# faun-two-layer-lipo-v1_0.net
KiCad netlist of a schematic drawn in EAGLE
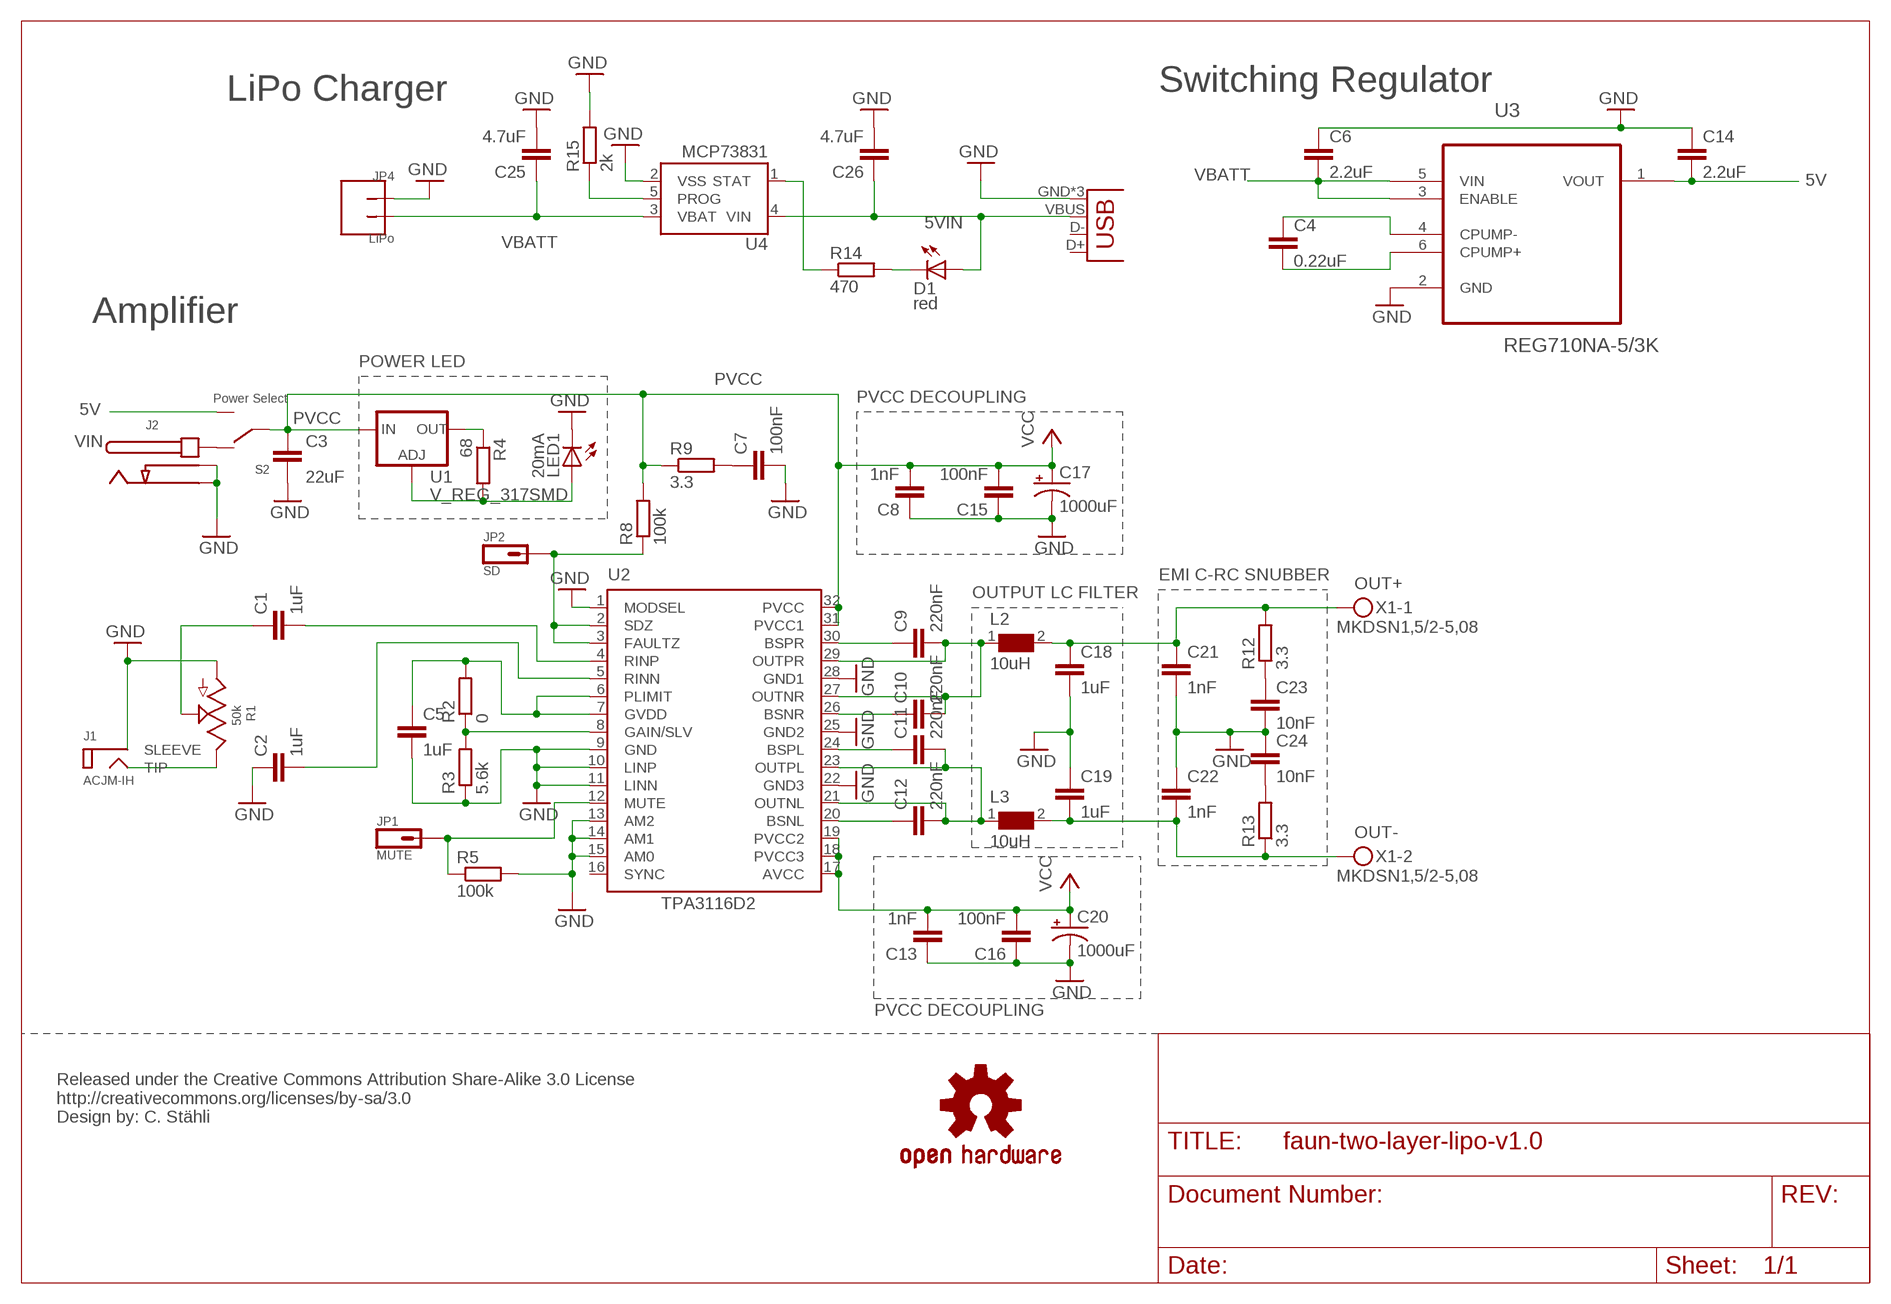
[diagram p0: schematic, sheet 1]

(export (version "E")
  (design (tool "Eeschema 10.0.6"))
  (components
    (comp (ref "C1")
      (value "1uF")
      (footprint "eagle-import:C1206")
      (libsource (lib "eagle-import") (part "C-EUC1206"))
    )
    (comp (ref "C2")
      (value "1uF")
      (footprint "eagle-import:C1206")
      (libsource (lib "eagle-import") (part "C-EUC1206"))
    )
    (comp (ref "C3")
      (value "22uF")
      (footprint "eagle-import:C1206")
      (libsource (lib "eagle-import") (part "C-EUC1206"))
    )
    (comp (ref "C4")
      (value "0.22uF")
      (footprint "eagle-import:C1206")
      (libsource (lib "eagle-import") (part "C-EUC1206"))
    )
    (comp (ref "C5")
      (value "1uF")
      (footprint "eagle-import:C1206")
      (libsource (lib "eagle-import") (part "C-EUC1206"))
    )
    (comp (ref "C6")
      (value "2.2uF")
      (footprint "eagle-import:C1206")
      (libsource (lib "eagle-import") (part "C-EUC1206"))
    )
    (comp (ref "C7")
      (value "100nF")
      (footprint "eagle-import:C1206")
      (libsource (lib "eagle-import") (part "C-EUC1206"))
    )
    (comp (ref "C8")
      (value "1nF")
      (footprint "eagle-import:C1206")
      (libsource (lib "eagle-import") (part "C-EUC1206"))
    )
    (comp (ref "C9")
      (value "220nF")
      (footprint "eagle-import:C1206")
      (libsource (lib "eagle-import") (part "C-EUC1206"))
    )
    (comp (ref "C10")
      (value "220nF")
      (footprint "eagle-import:C1206")
      (libsource (lib "eagle-import") (part "C-EUC1206"))
    )
    (comp (ref "C11")
      (value "220nF")
      (footprint "eagle-import:C1206")
      (libsource (lib "eagle-import") (part "C-EUC1206"))
    )
    (comp (ref "C12")
      (value "220nF")
      (footprint "eagle-import:C1206")
      (libsource (lib "eagle-import") (part "C-EUC1206"))
    )
    (comp (ref "C13")
      (value "1nF")
      (footprint "eagle-import:C1206")
      (libsource (lib "eagle-import") (part "C-EUC1206"))
    )
    (comp (ref "C14")
      (value "2.2uF")
      (footprint "eagle-import:C1206")
      (libsource (lib "eagle-import") (part "C-EUC1206"))
    )
    (comp (ref "C15")
      (value "100nF")
      (footprint "eagle-import:C1206")
      (libsource (lib "eagle-import") (part "C-EUC1206"))
    )
    (comp (ref "C16")
      (value "100nF")
      (footprint "eagle-import:C1206")
      (libsource (lib "eagle-import") (part "C-EUC1206"))
    )
    (comp (ref "C17")
      (value "1000uF")
      (footprint "eagle-import:UES1E102MHM")
      (libsource (lib "eagle-import") (part "UES1E102MHM"))
    )
    (comp (ref "C18")
      (value "1uF")
      (footprint "eagle-import:C1206")
      (libsource (lib "eagle-import") (part "C-EUC1206"))
    )
    (comp (ref "C19")
      (value "1uF")
      (footprint "eagle-import:C1206")
      (libsource (lib "eagle-import") (part "C-EUC1206"))
    )
    (comp (ref "C20")
      (value "1000uF")
      (footprint "eagle-import:UES1E102MHM")
      (libsource (lib "eagle-import") (part "UES1E102MHM"))
    )
    (comp (ref "C21")
      (value "1nF")
      (footprint "eagle-import:C1206")
      (libsource (lib "eagle-import") (part "C-EUC1206"))
    )
    (comp (ref "C22")
      (value "1nF")
      (footprint "eagle-import:C1206")
      (libsource (lib "eagle-import") (part "C-EUC1206"))
    )
    (comp (ref "C23")
      (value "10nF")
      (footprint "eagle-import:C1206")
      (libsource (lib "eagle-import") (part "C-EUC1206"))
    )
    (comp (ref "C24")
      (value "10nF")
      (footprint "eagle-import:C1206")
      (libsource (lib "eagle-import") (part "C-EUC1206"))
    )
    (comp (ref "C25")
      (value "4.7uF")
      (footprint "eagle-import:C1206")
      (libsource (lib "eagle-import") (part "C-EUC1206"))
    )
    (comp (ref "C26")
      (value "4.7uF")
      (footprint "eagle-import:C1206")
      (libsource (lib "eagle-import") (part "C-EUC1206"))
    )
    (comp (ref "D1")
      (value "red")
      (footprint "eagle-import:LED-1206")
      (libsource (lib "eagle-import") (part "LED1206"))
    )
    (comp (ref "J1")
      (value "ACJM-IH")
      (footprint "eagle-import:ACJM-IH")
      (libsource (lib "eagle-import") (part "ACJM-IH"))
    )
    (comp (ref "J2")
      (value "PJ-102AH")
      (footprint "eagle-import:PJ-102AH")
      (libsource (lib "eagle-import") (part "PJ-102AH"))
    )
    (comp (ref "JP1")
      (value "MUTE")
      (footprint "eagle-import:PAD-1.5X4.5")
      (libsource (lib "eagle-import") (part "M01SMD-4.5X1.5"))
    )
    (comp (ref "JP2")
      (value "SD")
      (footprint "eagle-import:PAD-1.5X4.5")
      (libsource (lib "eagle-import") (part "M01SMD-4.5X1.5"))
    )
    (comp (ref "JP4")
      (value "LiPo")
      (footprint "eagle-import:1778764")
      (libsource (lib "eagle-import") (part "1778764"))
    )
    (comp (ref "L2")
      (value "10uH")
      (footprint "eagle-import:WE-PD_1260_1245_1280_1210")
      (libsource (lib "eagle-import") (part "WE-PD_1260/1245/1280/1210"))
    )
    (comp (ref "L3")
      (value "10uH")
      (footprint "eagle-import:WE-PD_1260_1245_1280_1210")
      (libsource (lib "eagle-import") (part "WE-PD_1260/1245/1280/1210"))
    )
    (comp (ref "LED1")
      (value "20mA")
      (footprint "eagle-import:LED-1206")
      (libsource (lib "eagle-import") (part "faun_LED1206"))
    )
    (comp (ref "OPEN_HARDWARE_LOGO")
      (value "OSHW-LOGOL")
      (footprint "eagle-import:OSHW-LOGO-L")
      (libsource (lib "eagle-import") (part "OSHW-LOGOL"))
    )
    (comp (ref "OPEN_HARDWARE_LOGO_TOP")
      (value "OSHW-LOGOL")
      (footprint "eagle-import:OSHW-LOGO-L")
      (libsource (lib "eagle-import") (part "OSHW-LOGOL"))
    )
    (comp (ref "R1")
      (value "50k")
      (footprint "eagle-import:PTD902-2015K")
      (libsource (lib "eagle-import") (part "PTD902-2015K-A503"))
    )
    (comp (ref "R2")
      (value "0")
      (footprint "eagle-import:R1206")
      (libsource (lib "eagle-import") (part "R-EU_R1206"))
    )
    (comp (ref "R3")
      (value "5.6k")
      (footprint "eagle-import:R1206")
      (libsource (lib "eagle-import") (part "R-EU_R1206"))
    )
    (comp (ref "R4")
      (value "68")
      (footprint "eagle-import:R1206")
      (libsource (lib "eagle-import") (part "R-EU_R1206"))
    )
    (comp (ref "R5")
      (value "100k")
      (footprint "eagle-import:R1206")
      (libsource (lib "eagle-import") (part "R-EU_R1206"))
    )
    (comp (ref "R8")
      (value "100k")
      (footprint "eagle-import:R1206")
      (libsource (lib "eagle-import") (part "R-EU_R1206"))
    )
    (comp (ref "R9")
      (value "3.3")
      (footprint "eagle-import:R1206")
      (libsource (lib "eagle-import") (part "R-EU_R1206"))
    )
    (comp (ref "R12")
      (value "3.3")
      (footprint "eagle-import:R1206")
      (libsource (lib "eagle-import") (part "R-EU_R1206"))
    )
    (comp (ref "R13")
      (value "3.3")
      (footprint "eagle-import:R1206")
      (libsource (lib "eagle-import") (part "R-EU_R1206"))
    )
    (comp (ref "R14")
      (value "470")
      (footprint "eagle-import:R1206")
      (libsource (lib "eagle-import") (part "R-EU_R1206"))
    )
    (comp (ref "R15")
      (value "2k")
      (footprint "eagle-import:R1206")
      (libsource (lib "eagle-import") (part "R-EU_R1206"))
    )
    (comp (ref "S2")
      (value "Power Select")
      (footprint "eagle-import:MS-100845")
      (libsource (lib "eagle-import") (part "MS-100845"))
    )
    (comp (ref "U1")
      (value "V_REG_317SMD")
      (footprint "eagle-import:SOT223")
      (libsource (lib "eagle-import") (part "V_REG_317SMD"))
    )
    (comp (ref "U2")
      (value "TPA3116D2")
      (footprint "eagle-import:TPA3116D2")
      (libsource (lib "eagle-import") (part "TPA3116D2"))
    )
    (comp (ref "U3")
      (value "REG710NA-5/3K")
      (footprint "eagle-import:SOT95P280X145-6N")
      (libsource (lib "eagle-import") (part "REG710NA-5/3K"))
    )
    (comp (ref "U4")
      (value "MCP73831")
      (footprint "eagle-import:SOT23-5")
      (libsource (lib "eagle-import") (part "MCP73831"))
    )
    (comp (ref "X1")
      (value "MKDSN1,5/2-5,08")
      (footprint "eagle-import:MKDSN1,5_2-5,08")
      (fields (field (name "MPN") "MKDSN 1,5/2-5.08"))
      (libsource (lib "eagle-import") (part "MKDSN1,5/2-5,08"))
    )
    (comp (ref "X2")
      (value "USB-MICROB")
      (footprint "eagle-import:USB-MICROB")
      (libsource (lib "eagle-import") (part "USB-MICROB"))
    )
  )
  (nets
    (net (code "1") (name "/5V") (class "Default")
      (node (ref "C14") (pin "2") (pinfunction "2_2") (pintype "passive"))
      (node (ref "S2") (pin "P$3") (pinfunction "P$3_P$3") (pintype "input"))
      (node (ref "U3") (pin "1") (pinfunction "VOUT_1") (pintype "output"))
    )
    (net (code "2") (name "/5VIN") (class "Default")
      (node (ref "C26") (pin "1") (pinfunction "1_1") (pintype "passive"))
      (node (ref "D1") (pin "A") (pinfunction "A_A") (pintype "passive"))
      (node (ref "U4") (pin "4") (pinfunction "VIN_4") (pintype "power_in"))
      (node (ref "X2") (pin "VBUS") (pinfunction "VBUS_VBUS") (pintype "bidirectional"))
    )
    (net (code "3") (name "/OUT+") (class "Default")
      (node (ref "C18") (pin "1") (pinfunction "1_1") (pintype "passive"))
      (node (ref "C21") (pin "1") (pinfunction "1_1") (pintype "passive"))
      (node (ref "L2") (pin "2") (pinfunction "2_2") (pintype "passive"))
      (node (ref "R12") (pin "2") (pinfunction "2_2") (pintype "passive"))
      (node (ref "X1") (pin "1") (pinfunction "KL_1") (pintype "passive"))
    )
    (net (code "4") (name "/OUT-") (class "Default")
      (node (ref "C19") (pin "2") (pinfunction "2_2") (pintype "passive"))
      (node (ref "C22") (pin "2") (pinfunction "2_2") (pintype "passive"))
      (node (ref "L3") (pin "2") (pinfunction "2_2") (pintype "passive"))
      (node (ref "R13") (pin "1") (pinfunction "1_1") (pintype "passive"))
      (node (ref "X1") (pin "2") (pinfunction "KL_2") (pintype "passive"))
    )
    (net (code "5") (name "/VBATT") (class "Default")
      (node (ref "C25") (pin "1") (pinfunction "1_1") (pintype "passive"))
      (node (ref "C6") (pin "2") (pinfunction "2_2") (pintype "passive"))
      (node (ref "JP4") (pin "2") (pinfunction "2_2") (pintype "bidirectional"))
      (node (ref "U3") (pin "3") (pinfunction "ENABLE_3") (pintype "input"))
      (node (ref "U3") (pin "5") (pinfunction "VIN_5") (pintype "input"))
      (node (ref "U4") (pin "3") (pinfunction "VBAT_3") (pintype "power_in"))
    )
    (net (code "7") (name "/VIN") (class "Default")
      (node (ref "J2") (pin "VCC") (pinfunction "P$1_VCC") (pintype "bidirectional"))
      (node (ref "S2") (pin "P$1") (pinfunction "P$1_P$1") (pintype "input"))
    )
    (net (code "8") (name "GND") (class "Default")
      (node (ref "C13") (pin "1") (pinfunction "1_1") (pintype "passive"))
      (node (ref "C14") (pin "1") (pinfunction "1_1") (pintype "passive"))
      (node (ref "C15") (pin "1") (pinfunction "1_1") (pintype "passive"))
      (node (ref "C16") (pin "1") (pinfunction "1_1") (pintype "passive"))
      (node (ref "C17") (pin "-") (pinfunction "-_-") (pintype "passive"))
      (node (ref "C18") (pin "2") (pinfunction "2_2") (pintype "passive"))
      (node (ref "C19") (pin "1") (pinfunction "1_1") (pintype "passive"))
      (node (ref "C2") (pin "1") (pinfunction "1_1") (pintype "passive"))
      (node (ref "C20") (pin "-") (pinfunction "-_-") (pintype "passive"))
      (node (ref "C21") (pin "2") (pinfunction "2_2") (pintype "passive"))
      (node (ref "C22") (pin "1") (pinfunction "1_1") (pintype "passive"))
      (node (ref "C23") (pin "2") (pinfunction "2_2") (pintype "passive"))
      (node (ref "C24") (pin "1") (pinfunction "1_1") (pintype "passive"))
      (node (ref "C25") (pin "2") (pinfunction "2_2") (pintype "passive"))
      (node (ref "C26") (pin "2") (pinfunction "2_2") (pintype "passive"))
      (node (ref "C3") (pin "2") (pinfunction "2_2") (pintype "passive"))
      (node (ref "C5") (pin "2") (pinfunction "2_2") (pintype "passive"))
      (node (ref "C6") (pin "1") (pinfunction "1_1") (pintype "passive"))
      (node (ref "C7") (pin "2") (pinfunction "2_2") (pintype "passive"))
      (node (ref "C8") (pin "1") (pinfunction "1_1") (pintype "passive"))
      (node (ref "J1") (pin "SLEEVE@1") (pinfunction "SLEEVE_SLEEVE@1") (pintype "bidirectional"))
      (node (ref "J1") (pin "SLEEVE@2") (pinfunction "SLEEVE_SLEEVE@2") (pintype "bidirectional"))
      (node (ref "J2") (pin "GND@1") (pinfunction "P$2_GND@1") (pintype "bidirectional"))
      (node (ref "J2") (pin "GND@2") (pinfunction "P$3_GND@2") (pintype "bidirectional"))
      (node (ref "JP4") (pin "1") (pinfunction "1_1") (pintype "output"))
      (node (ref "LED1") (pin "C") (pinfunction "C_C") (pintype "passive"))
      (node (ref "R1") (pin "1") (pinfunction "1_1") (pintype "bidirectional"))
      (node (ref "R1") (pin "1'") (pinfunction "1_1'") (pintype "bidirectional"))
      (node (ref "R15") (pin "2") (pinfunction "2_2") (pintype "passive"))
      (node (ref "R3") (pin "1") (pinfunction "1_1") (pintype "passive"))
      (node (ref "R5") (pin "2") (pinfunction "2_2") (pintype "passive"))
      (node (ref "U2") (pin "1") (pinfunction "MODSEL_1") (pintype "input"))
      (node (ref "U2") (pin "10") (pinfunction "LINP_10") (pintype "input"))
      (node (ref "U2") (pin "11") (pinfunction "LINN_11") (pintype "input"))
      (node (ref "U2") (pin "13") (pinfunction "AM2_13") (pintype "input"))
      (node (ref "U2") (pin "14") (pinfunction "AM1_14") (pintype "input"))
      (node (ref "U2") (pin "15") (pinfunction "AM0_15") (pintype "input"))
      (node (ref "U2") (pin "22") (pinfunction "GND3_22") (pintype "input"))
      (node (ref "U2") (pin "25") (pinfunction "GND2_25") (pintype "input"))
      (node (ref "U2") (pin "28") (pinfunction "GND1_28") (pintype "input"))
      (node (ref "U2") (pin "9") (pinfunction "GND_9") (pintype "input"))
      (node (ref "U3") (pin "2") (pinfunction "GND_2") (pintype "passive"))
      (node (ref "U4") (pin "2") (pinfunction "VSS_2") (pintype "power_in"))
      (node (ref "X2") (pin "GND") (pinfunction "GND_GND") (pintype "bidirectional"))
      (node (ref "X2") (pin "MT1") (pinfunction "GND_MT1") (pintype "bidirectional"))
      (node (ref "X2") (pin "MT2") (pinfunction "GND_MT2") (pintype "bidirectional"))
    )
    (net (code "9") (name "Net-(C1-Pad1)") (class "Default")
      (node (ref "C1") (pin "1") (pinfunction "1_1") (pintype "passive"))
      (node (ref "R1") (pin "2") (pinfunction "2_2") (pintype "bidirectional"))
      (node (ref "R1") (pin "2'") (pinfunction "2_2'") (pintype "bidirectional"))
    )
    (net (code "10") (name "Net-(C7-Pad1)") (class "Default")
      (node (ref "C7") (pin "1") (pinfunction "1_1") (pintype "passive"))
      (node (ref "R9") (pin "2") (pinfunction "2_2") (pintype "passive"))
    )
    (net (code "11") (name "Net-(C23-Pad1)") (class "Default")
      (node (ref "C23") (pin "1") (pinfunction "1_1") (pintype "passive"))
      (node (ref "R12") (pin "1") (pinfunction "1_1") (pintype "passive"))
    )
    (net (code "12") (name "Net-(C24-Pad2)") (class "Default")
      (node (ref "C24") (pin "2") (pinfunction "2_2") (pintype "passive"))
      (node (ref "R13") (pin "2") (pinfunction "2_2") (pintype "passive"))
    )
    (net (code "13") (name "Net-(D1-PadC)") (class "Default")
      (node (ref "D1") (pin "C") (pinfunction "C_C") (pintype "passive"))
      (node (ref "R14") (pin "2") (pinfunction "2_2") (pintype "passive"))
    )
    (net (code "14") (name "Net-(J1-TIP-PadTIP@1)") (class "Default")
      (node (ref "J1") (pin "TIP@1") (pinfunction "TIP_TIP@1") (pintype "input"))
      (node (ref "J1") (pin "TIP@2") (pinfunction "TIP_TIP@2") (pintype "input"))
      (node (ref "R1") (pin "3") (pinfunction "3_3") (pintype "bidirectional"))
      (node (ref "R1") (pin "3'") (pinfunction "3_3'") (pintype "bidirectional"))
    )
    (net (code "15") (name "Net-(JP1-1)") (class "Default")
      (node (ref "JP1") (pin "P$1") (pinfunction "1_P$1") (pintype "passive"))
      (node (ref "R5") (pin "1") (pinfunction "1_1") (pintype "passive"))
      (node (ref "U2") (pin "12") (pinfunction "MUTE_12") (pintype "input"))
    )
    (net (code "16") (name "Net-(JP2-1)") (class "Default")
      (node (ref "JP2") (pin "P$1") (pinfunction "1_P$1") (pintype "passive"))
      (node (ref "R8") (pin "1") (pinfunction "1_1") (pintype "passive"))
      (node (ref "U2") (pin "2") (pinfunction "SDZ_2") (pintype "input"))
      (node (ref "U2") (pin "3") (pinfunction "FAULTZ_3") (pintype "input"))
    )
    (net (code "17") (name "Net-(U1-ADJ)") (class "Default")
      (node (ref "LED1") (pin "A") (pinfunction "A_A") (pintype "passive"))
      (node (ref "R4") (pin "2") (pinfunction "2_2") (pintype "passive"))
      (node (ref "U1") (pin "1") (pinfunction "ADJ_1") (pintype "input"))
    )
    (net (code "18") (name "Net-(U1-OUT)") (class "Default")
      (node (ref "R4") (pin "1") (pinfunction "1_1") (pintype "passive"))
      (node (ref "U1") (pin "2") (pinfunction "OUT_2") (pintype "output"))
    )
    (net (code "19") (name "Net-(U2-BSNL)") (class "Default")
      (node (ref "C12") (pin "1") (pinfunction "1_1") (pintype "passive"))
      (node (ref "U2") (pin "20") (pinfunction "BSNL_20") (pintype "input"))
    )
    (net (code "20") (name "Net-(U2-BSNR)") (class "Default")
      (node (ref "C10") (pin "1") (pinfunction "1_1") (pintype "passive"))
      (node (ref "U2") (pin "26") (pinfunction "BSNR_26") (pintype "input"))
    )
    (net (code "21") (name "Net-(U2-BSPL)") (class "Default")
      (node (ref "C11") (pin "1") (pinfunction "1_1") (pintype "passive"))
      (node (ref "U2") (pin "24") (pinfunction "BSPL_24") (pintype "input"))
    )
    (net (code "22") (name "Net-(U2-BSPR)") (class "Default")
      (node (ref "C9") (pin "1") (pinfunction "1_1") (pintype "passive"))
      (node (ref "U2") (pin "30") (pinfunction "BSPR_30") (pintype "input"))
    )
    (net (code "23") (name "Net-(U2-GAIN{slash}SLV)") (class "Default")
      (node (ref "R2") (pin "1") (pinfunction "1_1") (pintype "passive"))
      (node (ref "R3") (pin "2") (pinfunction "2_2") (pintype "passive"))
      (node (ref "U2") (pin "8") (pinfunction "GAIN/SLV_8") (pintype "input"))
    )
    (net (code "24") (name "Net-(U2-GVDD)") (class "Default")
      (node (ref "C5") (pin "1") (pinfunction "1_1") (pintype "passive"))
      (node (ref "R2") (pin "2") (pinfunction "2_2") (pintype "passive"))
      (node (ref "U2") (pin "6") (pinfunction "PLIMIT_6") (pintype "input"))
      (node (ref "U2") (pin "7") (pinfunction "GVDD_7") (pintype "input"))
    )
    (net (code "25") (name "Net-(U2-OUTNL)") (class "Default")
      (node (ref "C11") (pin "2") (pinfunction "2_2") (pintype "passive"))
      (node (ref "C12") (pin "2") (pinfunction "2_2") (pintype "passive"))
      (node (ref "L3") (pin "1") (pinfunction "1_1") (pintype "passive"))
      (node (ref "U2") (pin "21") (pinfunction "OUTNL_21") (pintype "input"))
      (node (ref "U2") (pin "23") (pinfunction "OUTPL_23") (pintype "input"))
    )
    (net (code "26") (name "Net-(U2-OUTNR)") (class "Default")
      (node (ref "C10") (pin "2") (pinfunction "2_2") (pintype "passive"))
      (node (ref "C9") (pin "2") (pinfunction "2_2") (pintype "passive"))
      (node (ref "L2") (pin "1") (pinfunction "1_1") (pintype "passive"))
      (node (ref "U2") (pin "27") (pinfunction "OUTNR_27") (pintype "input"))
      (node (ref "U2") (pin "29") (pinfunction "OUTPR_29") (pintype "input"))
    )
    (net (code "27") (name "Net-(U2-RINN)") (class "Default")
      (node (ref "C2") (pin "2") (pinfunction "2_2") (pintype "passive"))
      (node (ref "U2") (pin "5") (pinfunction "RINN_5") (pintype "input"))
    )
    (net (code "28") (name "Net-(U2-RINP)") (class "Default")
      (node (ref "C1") (pin "2") (pinfunction "2_2") (pintype "passive"))
      (node (ref "U2") (pin "4") (pinfunction "RINP_4") (pintype "input"))
    )
    (net (code "29") (name "Net-(U3-CPUMP+)") (class "Default")
      (node (ref "C4") (pin "2") (pinfunction "2_2") (pintype "passive"))
      (node (ref "U3") (pin "6") (pinfunction "CPUMP+_6") (pintype "input"))
    )
    (net (code "30") (name "Net-(U3-CPUMP-)") (class "Default")
      (node (ref "C4") (pin "1") (pinfunction "1_1") (pintype "passive"))
      (node (ref "U3") (pin "4") (pinfunction "CPUMP-_4") (pintype "input"))
    )
    (net (code "31") (name "Net-(U4-PROG)") (class "Default")
      (node (ref "R15") (pin "1") (pinfunction "1_1") (pintype "passive"))
      (node (ref "U4") (pin "5") (pinfunction "PROG_5") (pintype "input"))
    )
    (net (code "32") (name "Net-(U4-STAT)") (class "Default")
      (node (ref "R14") (pin "1") (pinfunction "1_1") (pintype "passive"))
      (node (ref "U4") (pin "1") (pinfunction "STAT_1") (pintype "output"))
    )
    (net (code "33") (name "VCC") (class "Default")
      (node (ref "C13") (pin "2") (pinfunction "2_2") (pintype "passive"))
      (node (ref "C15") (pin "2") (pinfunction "2_2") (pintype "passive"))
      (node (ref "C16") (pin "2") (pinfunction "2_2") (pintype "passive"))
      (node (ref "C17") (pin "+") (pinfunction "+_+") (pintype "passive"))
      (node (ref "C20") (pin "+") (pinfunction "+_+") (pintype "passive"))
      (node (ref "C3") (pin "1") (pinfunction "1_1") (pintype "passive"))
      (node (ref "C8") (pin "2") (pinfunction "2_2") (pintype "passive"))
      (node (ref "R8") (pin "2") (pinfunction "2_2") (pintype "passive"))
      (node (ref "R9") (pin "1") (pinfunction "1_1") (pintype "passive"))
      (node (ref "S2") (pin "P$2") (pinfunction "COMM_P$2") (pintype "bidirectional"))
      (node (ref "U1") (pin "3") (pinfunction "IN_3") (pintype "input"))
      (node (ref "U2") (pin "17") (pinfunction "AVCC_17") (pintype "input"))
      (node (ref "U2") (pin "18") (pinfunction "PVCC3_18") (pintype "input"))
      (node (ref "U2") (pin "19") (pinfunction "PVCC2_19") (pintype "input"))
      (node (ref "U2") (pin "31") (pinfunction "PVCC1_31") (pintype "input"))
      (node (ref "U2") (pin "32") (pinfunction "PVCC_32") (pintype "input"))
    )
    (net (code "34") (name "unconnected-(U2-SYNC-Pad16)") (class "Default")
      (node (ref "U2") (pin "16") (pinfunction "SYNC_16") (pintype "input"))
    )
    (net (code "35") (name "unconnected-(X2-PadD+)") (class "Default")
      (node (ref "X2") (pin "D+") (pinfunction "D+_D+") (pintype "bidirectional"))
    )
    (net (code "36") (name "unconnected-(X2-PadD-)") (class "Default")
      (node (ref "X2") (pin "D-") (pinfunction "D-_D-") (pintype "bidirectional"))
    )
  )
)
